# WS2812_MATRIX_1.net
KiCad netlist of a schematic drawn in Altium Designer
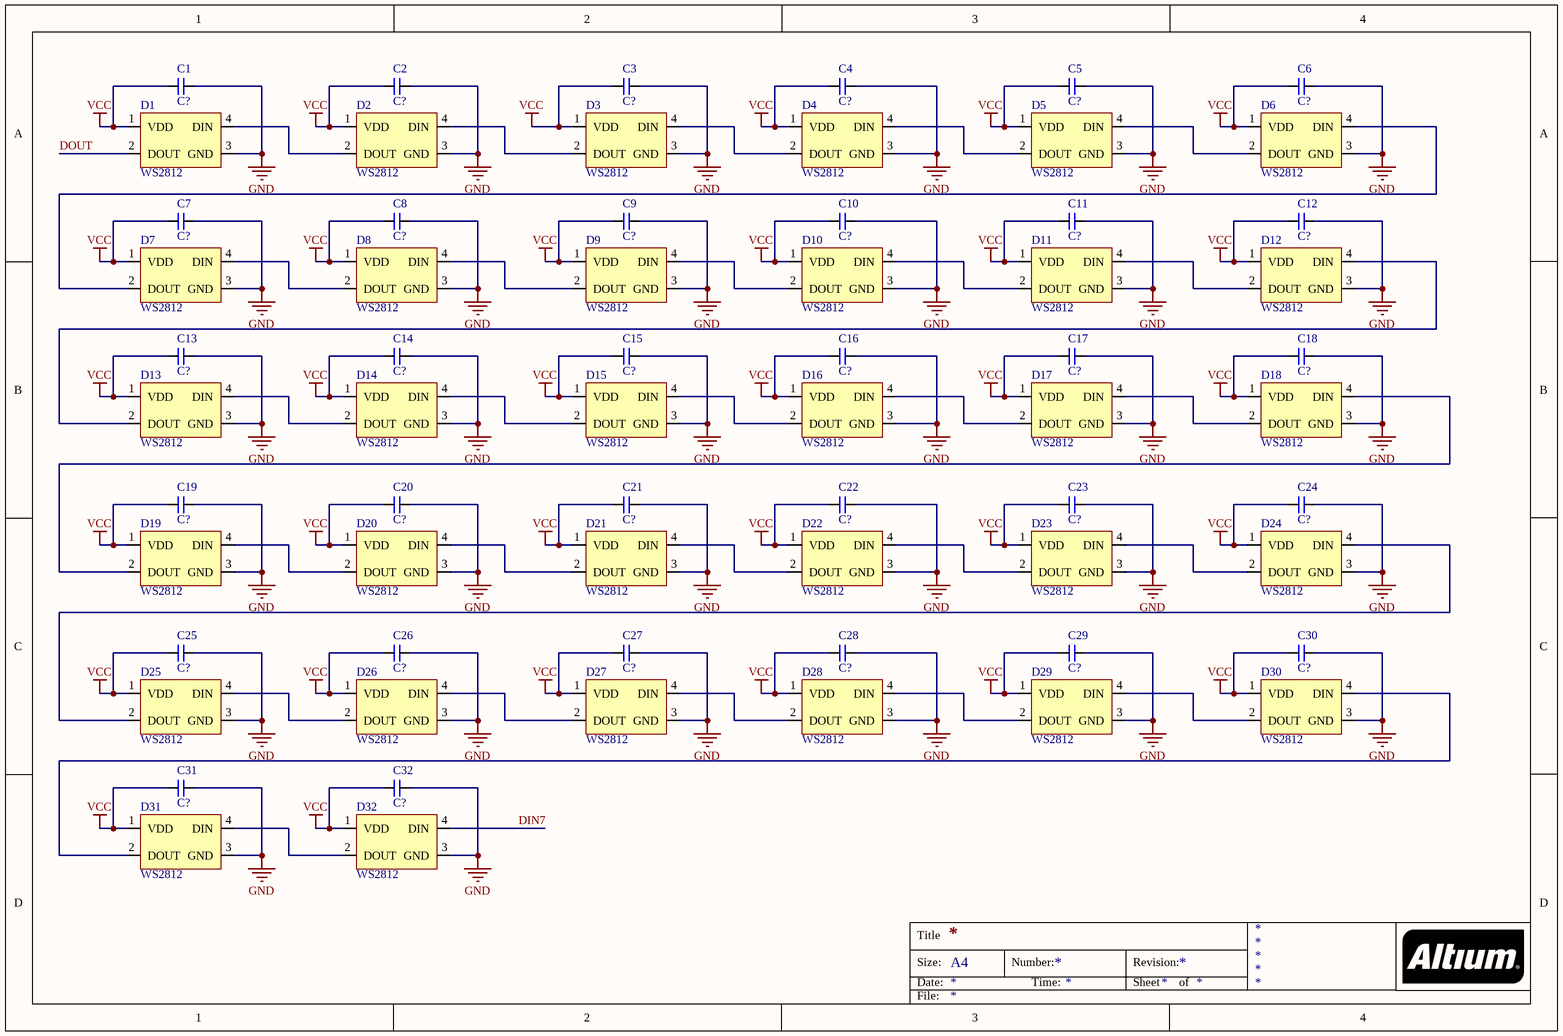
[diagram p0: WS2812_MATRIX_1.SchDoc]

(export (version "E")
  (design (tool "Eeschema 10.0.6"))
  (components
    (comp (ref "C1")
      (value "C?")
      (footprint "C0603")
      (description "Cap")
      (libsource (lib "SCH_Bacsic") (part "CAP"))
    )
    (comp (ref "C2")
      (value "C?")
      (footprint "C0603")
      (description "Cap")
      (libsource (lib "SCH_Bacsic") (part "CAP"))
    )
    (comp (ref "C3")
      (value "C?")
      (footprint "C0603")
      (description "Cap")
      (libsource (lib "SCH_Bacsic") (part "CAP"))
    )
    (comp (ref "C4")
      (value "C?")
      (footprint "C0603")
      (description "Cap")
      (libsource (lib "SCH_Bacsic") (part "CAP"))
    )
    (comp (ref "C5")
      (value "C?")
      (footprint "C0603")
      (description "Cap")
      (libsource (lib "SCH_Bacsic") (part "CAP"))
    )
    (comp (ref "C6")
      (value "C?")
      (footprint "C0603")
      (description "Cap")
      (libsource (lib "SCH_Bacsic") (part "CAP"))
    )
    (comp (ref "C7")
      (value "C?")
      (footprint "C0603")
      (description "Cap")
      (libsource (lib "SCH_Bacsic") (part "CAP"))
    )
    (comp (ref "C8")
      (value "C?")
      (footprint "C0603")
      (description "Cap")
      (libsource (lib "SCH_Bacsic") (part "CAP"))
    )
    (comp (ref "C9")
      (value "C?")
      (footprint "C0603")
      (description "Cap")
      (libsource (lib "SCH_Bacsic") (part "CAP"))
    )
    (comp (ref "C10")
      (value "C?")
      (footprint "C0603")
      (description "Cap")
      (libsource (lib "SCH_Bacsic") (part "CAP"))
    )
    (comp (ref "C11")
      (value "C?")
      (footprint "C0603")
      (description "Cap")
      (libsource (lib "SCH_Bacsic") (part "CAP"))
    )
    (comp (ref "C12")
      (value "C?")
      (footprint "C0603")
      (description "Cap")
      (libsource (lib "SCH_Bacsic") (part "CAP"))
    )
    (comp (ref "C13")
      (value "C?")
      (footprint "C0603")
      (description "Cap")
      (libsource (lib "SCH_Bacsic") (part "CAP"))
    )
    (comp (ref "C14")
      (value "C?")
      (footprint "C0603")
      (description "Cap")
      (libsource (lib "SCH_Bacsic") (part "CAP"))
    )
    (comp (ref "C15")
      (value "C?")
      (footprint "C0603")
      (description "Cap")
      (libsource (lib "SCH_Bacsic") (part "CAP"))
    )
    (comp (ref "C16")
      (value "C?")
      (footprint "C0603")
      (description "Cap")
      (libsource (lib "SCH_Bacsic") (part "CAP"))
    )
    (comp (ref "C17")
      (value "C?")
      (footprint "C0603")
      (description "Cap")
      (libsource (lib "SCH_Bacsic") (part "CAP"))
    )
    (comp (ref "C18")
      (value "C?")
      (footprint "C0603")
      (description "Cap")
      (libsource (lib "SCH_Bacsic") (part "CAP"))
    )
    (comp (ref "C19")
      (value "C?")
      (footprint "C0603")
      (description "Cap")
      (libsource (lib "SCH_Bacsic") (part "CAP"))
    )
    (comp (ref "C20")
      (value "C?")
      (footprint "C0603")
      (description "Cap")
      (libsource (lib "SCH_Bacsic") (part "CAP"))
    )
    (comp (ref "C21")
      (value "C?")
      (footprint "C0603")
      (description "Cap")
      (libsource (lib "SCH_Bacsic") (part "CAP"))
    )
    (comp (ref "C22")
      (value "C?")
      (footprint "C0603")
      (description "Cap")
      (libsource (lib "SCH_Bacsic") (part "CAP"))
    )
    (comp (ref "C23")
      (value "C?")
      (footprint "C0603")
      (description "Cap")
      (libsource (lib "SCH_Bacsic") (part "CAP"))
    )
    (comp (ref "C24")
      (value "C?")
      (footprint "C0603")
      (description "Cap")
      (libsource (lib "SCH_Bacsic") (part "CAP"))
    )
    (comp (ref "C25")
      (value "C?")
      (footprint "C0603")
      (description "Cap")
      (libsource (lib "SCH_Bacsic") (part "CAP"))
    )
    (comp (ref "C26")
      (value "C?")
      (footprint "C0603")
      (description "Cap")
      (libsource (lib "SCH_Bacsic") (part "CAP"))
    )
    (comp (ref "C27")
      (value "C?")
      (footprint "C0603")
      (description "Cap")
      (libsource (lib "SCH_Bacsic") (part "CAP"))
    )
    (comp (ref "C28")
      (value "C?")
      (footprint "C0603")
      (description "Cap")
      (libsource (lib "SCH_Bacsic") (part "CAP"))
    )
    (comp (ref "C29")
      (value "C?")
      (footprint "C0603")
      (description "Cap")
      (libsource (lib "SCH_Bacsic") (part "CAP"))
    )
    (comp (ref "C30")
      (value "C?")
      (footprint "C0603")
      (description "Cap")
      (libsource (lib "SCH_Bacsic") (part "CAP"))
    )
    (comp (ref "C31")
      (value "C?")
      (footprint "C0603")
      (description "Cap")
      (libsource (lib "SCH_Bacsic") (part "CAP"))
    )
    (comp (ref "C32")
      (value "C?")
      (footprint "C0603")
      (description "Cap")
      (libsource (lib "SCH_Bacsic") (part "CAP"))
    )
    (comp (ref "D1")
      (value "WS2812")
      (footprint "WS2812_3528")
      (libsource (lib "SCH_Bacsic") (part "WS2812"))
    )
    (comp (ref "D2")
      (value "WS2812")
      (footprint "WS2812_3528")
      (libsource (lib "SCH_Bacsic") (part "WS2812"))
    )
    (comp (ref "D3")
      (value "WS2812")
      (footprint "WS2812_3528")
      (libsource (lib "SCH_Bacsic") (part "WS2812"))
    )
    (comp (ref "D4")
      (value "WS2812")
      (footprint "WS2812_3528")
      (libsource (lib "SCH_Bacsic") (part "WS2812"))
    )
    (comp (ref "D5")
      (value "WS2812")
      (footprint "WS2812_3528")
      (libsource (lib "SCH_Bacsic") (part "WS2812"))
    )
    (comp (ref "D6")
      (value "WS2812")
      (footprint "WS2812_3528")
      (libsource (lib "SCH_Bacsic") (part "WS2812"))
    )
    (comp (ref "D7")
      (value "WS2812")
      (footprint "WS2812_3528")
      (libsource (lib "SCH_Bacsic") (part "WS2812"))
    )
    (comp (ref "D8")
      (value "WS2812")
      (footprint "WS2812_3528")
      (libsource (lib "SCH_Bacsic") (part "WS2812"))
    )
    (comp (ref "D9")
      (value "WS2812")
      (footprint "WS2812_3528")
      (libsource (lib "SCH_Bacsic") (part "WS2812"))
    )
    (comp (ref "D10")
      (value "WS2812")
      (footprint "WS2812_3528")
      (libsource (lib "SCH_Bacsic") (part "WS2812"))
    )
    (comp (ref "D11")
      (value "WS2812")
      (footprint "WS2812_3528")
      (libsource (lib "SCH_Bacsic") (part "WS2812"))
    )
    (comp (ref "D12")
      (value "WS2812")
      (footprint "WS2812_3528")
      (libsource (lib "SCH_Bacsic") (part "WS2812"))
    )
    (comp (ref "D13")
      (value "WS2812")
      (footprint "WS2812_3528")
      (libsource (lib "SCH_Bacsic") (part "WS2812"))
    )
    (comp (ref "D14")
      (value "WS2812")
      (footprint "WS2812_3528")
      (libsource (lib "SCH_Bacsic") (part "WS2812"))
    )
    (comp (ref "D15")
      (value "WS2812")
      (footprint "WS2812_3528")
      (libsource (lib "SCH_Bacsic") (part "WS2812"))
    )
    (comp (ref "D16")
      (value "WS2812")
      (footprint "WS2812_3528")
      (libsource (lib "SCH_Bacsic") (part "WS2812"))
    )
    (comp (ref "D17")
      (value "WS2812")
      (footprint "WS2812_3528")
      (libsource (lib "SCH_Bacsic") (part "WS2812"))
    )
    (comp (ref "D18")
      (value "WS2812")
      (footprint "WS2812_3528")
      (libsource (lib "SCH_Bacsic") (part "WS2812"))
    )
    (comp (ref "D19")
      (value "WS2812")
      (footprint "WS2812_3528")
      (libsource (lib "SCH_Bacsic") (part "WS2812"))
    )
    (comp (ref "D20")
      (value "WS2812")
      (footprint "WS2812_3528")
      (libsource (lib "SCH_Bacsic") (part "WS2812"))
    )
    (comp (ref "D21")
      (value "WS2812")
      (footprint "WS2812_3528")
      (libsource (lib "SCH_Bacsic") (part "WS2812"))
    )
    (comp (ref "D22")
      (value "WS2812")
      (footprint "WS2812_3528")
      (libsource (lib "SCH_Bacsic") (part "WS2812"))
    )
    (comp (ref "D23")
      (value "WS2812")
      (footprint "WS2812_3528")
      (libsource (lib "SCH_Bacsic") (part "WS2812"))
    )
    (comp (ref "D24")
      (value "WS2812")
      (footprint "WS2812_3528")
      (libsource (lib "SCH_Bacsic") (part "WS2812"))
    )
    (comp (ref "D25")
      (value "WS2812")
      (footprint "WS2812_3528")
      (libsource (lib "SCH_Bacsic") (part "WS2812"))
    )
    (comp (ref "D26")
      (value "WS2812")
      (footprint "WS2812_3528")
      (libsource (lib "SCH_Bacsic") (part "WS2812"))
    )
    (comp (ref "D27")
      (value "WS2812")
      (footprint "WS2812_3528")
      (libsource (lib "SCH_Bacsic") (part "WS2812"))
    )
    (comp (ref "D28")
      (value "WS2812")
      (footprint "WS2812_3528")
      (libsource (lib "SCH_Bacsic") (part "WS2812"))
    )
    (comp (ref "D29")
      (value "WS2812")
      (footprint "WS2812_3528")
      (libsource (lib "SCH_Bacsic") (part "WS2812"))
    )
    (comp (ref "D30")
      (value "WS2812")
      (footprint "WS2812_3528")
      (libsource (lib "SCH_Bacsic") (part "WS2812"))
    )
    (comp (ref "D31")
      (value "WS2812")
      (footprint "WS2812_3528")
      (libsource (lib "SCH_Bacsic") (part "WS2812"))
    )
    (comp (ref "D32")
      (value "WS2812")
      (footprint "WS2812_3528")
      (libsource (lib "SCH_Bacsic") (part "WS2812"))
    )
  )
  (nets
    (net (code "1") (name "/DIN7") (class "Default")
      (node (ref "D32") (pin "4") (pinfunction "DIN_4") (pintype "passive"))
    )
    (net (code "2") (name "/DOUT") (class "Default")
      (node (ref "D1") (pin "2") (pinfunction "DOUT_2") (pintype "passive"))
    )
    (net (code "3") (name "GND") (class "Default")
      (node (ref "C1") (pin "2") (pintype "passive"))
      (node (ref "C10") (pin "2") (pintype "passive"))
      (node (ref "C11") (pin "2") (pintype "passive"))
      (node (ref "C12") (pin "2") (pintype "passive"))
      (node (ref "C13") (pin "2") (pintype "passive"))
      (node (ref "C14") (pin "2") (pintype "passive"))
      (node (ref "C15") (pin "2") (pintype "passive"))
      (node (ref "C16") (pin "2") (pintype "passive"))
      (node (ref "C17") (pin "2") (pintype "passive"))
      (node (ref "C18") (pin "2") (pintype "passive"))
      (node (ref "C19") (pin "2") (pintype "passive"))
      (node (ref "C2") (pin "2") (pintype "passive"))
      (node (ref "C20") (pin "2") (pintype "passive"))
      (node (ref "C21") (pin "2") (pintype "passive"))
      (node (ref "C22") (pin "2") (pintype "passive"))
      (node (ref "C23") (pin "2") (pintype "passive"))
      (node (ref "C24") (pin "2") (pintype "passive"))
      (node (ref "C25") (pin "2") (pintype "passive"))
      (node (ref "C26") (pin "2") (pintype "passive"))
      (node (ref "C27") (pin "2") (pintype "passive"))
      (node (ref "C28") (pin "2") (pintype "passive"))
      (node (ref "C29") (pin "2") (pintype "passive"))
      (node (ref "C3") (pin "2") (pintype "passive"))
      (node (ref "C30") (pin "2") (pintype "passive"))
      (node (ref "C31") (pin "2") (pintype "passive"))
      (node (ref "C32") (pin "2") (pintype "passive"))
      (node (ref "C4") (pin "2") (pintype "passive"))
      (node (ref "C5") (pin "2") (pintype "passive"))
      (node (ref "C6") (pin "2") (pintype "passive"))
      (node (ref "C7") (pin "2") (pintype "passive"))
      (node (ref "C8") (pin "2") (pintype "passive"))
      (node (ref "C9") (pin "2") (pintype "passive"))
      (node (ref "D1") (pin "3") (pinfunction "GND_3") (pintype "passive"))
      (node (ref "D10") (pin "3") (pinfunction "GND_3") (pintype "passive"))
      (node (ref "D11") (pin "3") (pinfunction "GND_3") (pintype "passive"))
      (node (ref "D12") (pin "3") (pinfunction "GND_3") (pintype "passive"))
      (node (ref "D13") (pin "3") (pinfunction "GND_3") (pintype "passive"))
      (node (ref "D14") (pin "3") (pinfunction "GND_3") (pintype "passive"))
      (node (ref "D15") (pin "3") (pinfunction "GND_3") (pintype "passive"))
      (node (ref "D16") (pin "3") (pinfunction "GND_3") (pintype "passive"))
      (node (ref "D17") (pin "3") (pinfunction "GND_3") (pintype "passive"))
      (node (ref "D18") (pin "3") (pinfunction "GND_3") (pintype "passive"))
      (node (ref "D19") (pin "3") (pinfunction "GND_3") (pintype "passive"))
      (node (ref "D2") (pin "3") (pinfunction "GND_3") (pintype "passive"))
      (node (ref "D20") (pin "3") (pinfunction "GND_3") (pintype "passive"))
      (node (ref "D21") (pin "3") (pinfunction "GND_3") (pintype "passive"))
      (node (ref "D22") (pin "3") (pinfunction "GND_3") (pintype "passive"))
      (node (ref "D23") (pin "3") (pinfunction "GND_3") (pintype "passive"))
      (node (ref "D24") (pin "3") (pinfunction "GND_3") (pintype "passive"))
      (node (ref "D25") (pin "3") (pinfunction "GND_3") (pintype "passive"))
      (node (ref "D26") (pin "3") (pinfunction "GND_3") (pintype "passive"))
      (node (ref "D27") (pin "3") (pinfunction "GND_3") (pintype "passive"))
      (node (ref "D28") (pin "3") (pinfunction "GND_3") (pintype "passive"))
      (node (ref "D29") (pin "3") (pinfunction "GND_3") (pintype "passive"))
      (node (ref "D3") (pin "3") (pinfunction "GND_3") (pintype "passive"))
      (node (ref "D30") (pin "3") (pinfunction "GND_3") (pintype "passive"))
      (node (ref "D31") (pin "3") (pinfunction "GND_3") (pintype "passive"))
      (node (ref "D32") (pin "3") (pinfunction "GND_3") (pintype "passive"))
      (node (ref "D4") (pin "3") (pinfunction "GND_3") (pintype "passive"))
      (node (ref "D5") (pin "3") (pinfunction "GND_3") (pintype "passive"))
      (node (ref "D6") (pin "3") (pinfunction "GND_3") (pintype "passive"))
      (node (ref "D7") (pin "3") (pinfunction "GND_3") (pintype "passive"))
      (node (ref "D8") (pin "3") (pinfunction "GND_3") (pintype "passive"))
      (node (ref "D9") (pin "3") (pinfunction "GND_3") (pintype "passive"))
    )
    (net (code "4") (name "Net-(D1-DIN)") (class "Default")
      (node (ref "D1") (pin "4") (pinfunction "DIN_4") (pintype "passive"))
      (node (ref "D2") (pin "2") (pinfunction "DOUT_2") (pintype "passive"))
    )
    (net (code "5") (name "Net-(D2-DIN)") (class "Default")
      (node (ref "D2") (pin "4") (pinfunction "DIN_4") (pintype "passive"))
      (node (ref "D3") (pin "2") (pinfunction "DOUT_2") (pintype "passive"))
    )
    (net (code "6") (name "Net-(D3-DIN)") (class "Default")
      (node (ref "D3") (pin "4") (pinfunction "DIN_4") (pintype "passive"))
      (node (ref "D4") (pin "2") (pinfunction "DOUT_2") (pintype "passive"))
    )
    (net (code "7") (name "Net-(D4-DIN)") (class "Default")
      (node (ref "D4") (pin "4") (pinfunction "DIN_4") (pintype "passive"))
      (node (ref "D5") (pin "2") (pinfunction "DOUT_2") (pintype "passive"))
    )
    (net (code "8") (name "Net-(D5-DIN)") (class "Default")
      (node (ref "D5") (pin "4") (pinfunction "DIN_4") (pintype "passive"))
      (node (ref "D6") (pin "2") (pinfunction "DOUT_2") (pintype "passive"))
    )
    (net (code "9") (name "Net-(D6-DIN)") (class "Default")
      (node (ref "D6") (pin "4") (pinfunction "DIN_4") (pintype "passive"))
      (node (ref "D7") (pin "2") (pinfunction "DOUT_2") (pintype "passive"))
    )
    (net (code "10") (name "Net-(D7-DIN)") (class "Default")
      (node (ref "D7") (pin "4") (pinfunction "DIN_4") (pintype "passive"))
      (node (ref "D8") (pin "2") (pinfunction "DOUT_2") (pintype "passive"))
    )
    (net (code "11") (name "Net-(D8-DIN)") (class "Default")
      (node (ref "D8") (pin "4") (pinfunction "DIN_4") (pintype "passive"))
      (node (ref "D9") (pin "2") (pinfunction "DOUT_2") (pintype "passive"))
    )
    (net (code "12") (name "Net-(D10-DIN)") (class "Default")
      (node (ref "D10") (pin "4") (pinfunction "DIN_4") (pintype "passive"))
      (node (ref "D11") (pin "2") (pinfunction "DOUT_2") (pintype "passive"))
    )
    (net (code "13") (name "Net-(D10-DOUT)") (class "Default")
      (node (ref "D10") (pin "2") (pinfunction "DOUT_2") (pintype "passive"))
      (node (ref "D9") (pin "4") (pinfunction "DIN_4") (pintype "passive"))
    )
    (net (code "14") (name "Net-(D11-DIN)") (class "Default")
      (node (ref "D11") (pin "4") (pinfunction "DIN_4") (pintype "passive"))
      (node (ref "D12") (pin "2") (pinfunction "DOUT_2") (pintype "passive"))
    )
    (net (code "15") (name "Net-(D12-DIN)") (class "Default")
      (node (ref "D12") (pin "4") (pinfunction "DIN_4") (pintype "passive"))
      (node (ref "D13") (pin "2") (pinfunction "DOUT_2") (pintype "passive"))
    )
    (net (code "16") (name "Net-(D13-DIN)") (class "Default")
      (node (ref "D13") (pin "4") (pinfunction "DIN_4") (pintype "passive"))
      (node (ref "D14") (pin "2") (pinfunction "DOUT_2") (pintype "passive"))
    )
    (net (code "17") (name "Net-(D14-DIN)") (class "Default")
      (node (ref "D14") (pin "4") (pinfunction "DIN_4") (pintype "passive"))
      (node (ref "D15") (pin "2") (pinfunction "DOUT_2") (pintype "passive"))
    )
    (net (code "18") (name "Net-(D15-DIN)") (class "Default")
      (node (ref "D15") (pin "4") (pinfunction "DIN_4") (pintype "passive"))
      (node (ref "D16") (pin "2") (pinfunction "DOUT_2") (pintype "passive"))
    )
    (net (code "19") (name "Net-(D16-DIN)") (class "Default")
      (node (ref "D16") (pin "4") (pinfunction "DIN_4") (pintype "passive"))
      (node (ref "D17") (pin "2") (pinfunction "DOUT_2") (pintype "passive"))
    )
    (net (code "20") (name "Net-(D17-DIN)") (class "Default")
      (node (ref "D17") (pin "4") (pinfunction "DIN_4") (pintype "passive"))
      (node (ref "D18") (pin "2") (pinfunction "DOUT_2") (pintype "passive"))
    )
    (net (code "21") (name "Net-(D18-DIN)") (class "Default")
      (node (ref "D18") (pin "4") (pinfunction "DIN_4") (pintype "passive"))
      (node (ref "D19") (pin "2") (pinfunction "DOUT_2") (pintype "passive"))
    )
    (net (code "22") (name "Net-(D19-DIN)") (class "Default")
      (node (ref "D19") (pin "4") (pinfunction "DIN_4") (pintype "passive"))
      (node (ref "D20") (pin "2") (pinfunction "DOUT_2") (pintype "passive"))
    )
    (net (code "23") (name "Net-(D20-DIN)") (class "Default")
      (node (ref "D20") (pin "4") (pinfunction "DIN_4") (pintype "passive"))
      (node (ref "D21") (pin "2") (pinfunction "DOUT_2") (pintype "passive"))
    )
    (net (code "24") (name "Net-(D21-DIN)") (class "Default")
      (node (ref "D21") (pin "4") (pinfunction "DIN_4") (pintype "passive"))
      (node (ref "D22") (pin "2") (pinfunction "DOUT_2") (pintype "passive"))
    )
    (net (code "25") (name "Net-(D22-DIN)") (class "Default")
      (node (ref "D22") (pin "4") (pinfunction "DIN_4") (pintype "passive"))
      (node (ref "D23") (pin "2") (pinfunction "DOUT_2") (pintype "passive"))
    )
    (net (code "26") (name "Net-(D23-DIN)") (class "Default")
      (node (ref "D23") (pin "4") (pinfunction "DIN_4") (pintype "passive"))
      (node (ref "D24") (pin "2") (pinfunction "DOUT_2") (pintype "passive"))
    )
    (net (code "27") (name "Net-(D24-DIN)") (class "Default")
      (node (ref "D24") (pin "4") (pinfunction "DIN_4") (pintype "passive"))
      (node (ref "D25") (pin "2") (pinfunction "DOUT_2") (pintype "passive"))
    )
    (net (code "28") (name "Net-(D25-DIN)") (class "Default")
      (node (ref "D25") (pin "4") (pinfunction "DIN_4") (pintype "passive"))
      (node (ref "D26") (pin "2") (pinfunction "DOUT_2") (pintype "passive"))
    )
    (net (code "29") (name "Net-(D26-DIN)") (class "Default")
      (node (ref "D26") (pin "4") (pinfunction "DIN_4") (pintype "passive"))
      (node (ref "D27") (pin "2") (pinfunction "DOUT_2") (pintype "passive"))
    )
    (net (code "30") (name "Net-(D27-DIN)") (class "Default")
      (node (ref "D27") (pin "4") (pinfunction "DIN_4") (pintype "passive"))
      (node (ref "D28") (pin "2") (pinfunction "DOUT_2") (pintype "passive"))
    )
    (net (code "31") (name "Net-(D28-DIN)") (class "Default")
      (node (ref "D28") (pin "4") (pinfunction "DIN_4") (pintype "passive"))
      (node (ref "D29") (pin "2") (pinfunction "DOUT_2") (pintype "passive"))
    )
    (net (code "32") (name "Net-(D29-DIN)") (class "Default")
      (node (ref "D29") (pin "4") (pinfunction "DIN_4") (pintype "passive"))
      (node (ref "D30") (pin "2") (pinfunction "DOUT_2") (pintype "passive"))
    )
    (net (code "33") (name "Net-(D30-DIN)") (class "Default")
      (node (ref "D30") (pin "4") (pinfunction "DIN_4") (pintype "passive"))
      (node (ref "D31") (pin "2") (pinfunction "DOUT_2") (pintype "passive"))
    )
    (net (code "34") (name "Net-(D31-DIN)") (class "Default")
      (node (ref "D31") (pin "4") (pinfunction "DIN_4") (pintype "passive"))
      (node (ref "D32") (pin "2") (pinfunction "DOUT_2") (pintype "passive"))
    )
    (net (code "35") (name "VCC") (class "Default")
      (node (ref "C1") (pin "1") (pintype "passive"))
      (node (ref "C10") (pin "1") (pintype "passive"))
      (node (ref "C11") (pin "1") (pintype "passive"))
      (node (ref "C12") (pin "1") (pintype "passive"))
      (node (ref "C13") (pin "1") (pintype "passive"))
      (node (ref "C14") (pin "1") (pintype "passive"))
      (node (ref "C15") (pin "1") (pintype "passive"))
      (node (ref "C16") (pin "1") (pintype "passive"))
      (node (ref "C17") (pin "1") (pintype "passive"))
      (node (ref "C18") (pin "1") (pintype "passive"))
      (node (ref "C19") (pin "1") (pintype "passive"))
      (node (ref "C2") (pin "1") (pintype "passive"))
      (node (ref "C20") (pin "1") (pintype "passive"))
      (node (ref "C21") (pin "1") (pintype "passive"))
      (node (ref "C22") (pin "1") (pintype "passive"))
      (node (ref "C23") (pin "1") (pintype "passive"))
      (node (ref "C24") (pin "1") (pintype "passive"))
      (node (ref "C25") (pin "1") (pintype "passive"))
      (node (ref "C26") (pin "1") (pintype "passive"))
      (node (ref "C27") (pin "1") (pintype "passive"))
      (node (ref "C28") (pin "1") (pintype "passive"))
      (node (ref "C29") (pin "1") (pintype "passive"))
      (node (ref "C3") (pin "1") (pintype "passive"))
      (node (ref "C30") (pin "1") (pintype "passive"))
      (node (ref "C31") (pin "1") (pintype "passive"))
      (node (ref "C32") (pin "1") (pintype "passive"))
      (node (ref "C4") (pin "1") (pintype "passive"))
      (node (ref "C5") (pin "1") (pintype "passive"))
      (node (ref "C6") (pin "1") (pintype "passive"))
      (node (ref "C7") (pin "1") (pintype "passive"))
      (node (ref "C8") (pin "1") (pintype "passive"))
      (node (ref "C9") (pin "1") (pintype "passive"))
      (node (ref "D1") (pin "1") (pinfunction "VDD_1") (pintype "passive"))
      (node (ref "D10") (pin "1") (pinfunction "VDD_1") (pintype "passive"))
      (node (ref "D11") (pin "1") (pinfunction "VDD_1") (pintype "passive"))
      (node (ref "D12") (pin "1") (pinfunction "VDD_1") (pintype "passive"))
      (node (ref "D13") (pin "1") (pinfunction "VDD_1") (pintype "passive"))
      (node (ref "D14") (pin "1") (pinfunction "VDD_1") (pintype "passive"))
      (node (ref "D15") (pin "1") (pinfunction "VDD_1") (pintype "passive"))
      (node (ref "D16") (pin "1") (pinfunction "VDD_1") (pintype "passive"))
      (node (ref "D17") (pin "1") (pinfunction "VDD_1") (pintype "passive"))
      (node (ref "D18") (pin "1") (pinfunction "VDD_1") (pintype "passive"))
      (node (ref "D19") (pin "1") (pinfunction "VDD_1") (pintype "passive"))
      (node (ref "D2") (pin "1") (pinfunction "VDD_1") (pintype "passive"))
      (node (ref "D20") (pin "1") (pinfunction "VDD_1") (pintype "passive"))
      (node (ref "D21") (pin "1") (pinfunction "VDD_1") (pintype "passive"))
      (node (ref "D22") (pin "1") (pinfunction "VDD_1") (pintype "passive"))
      (node (ref "D23") (pin "1") (pinfunction "VDD_1") (pintype "passive"))
      (node (ref "D24") (pin "1") (pinfunction "VDD_1") (pintype "passive"))
      (node (ref "D25") (pin "1") (pinfunction "VDD_1") (pintype "passive"))
      (node (ref "D26") (pin "1") (pinfunction "VDD_1") (pintype "passive"))
      (node (ref "D27") (pin "1") (pinfunction "VDD_1") (pintype "passive"))
      (node (ref "D28") (pin "1") (pinfunction "VDD_1") (pintype "passive"))
      (node (ref "D29") (pin "1") (pinfunction "VDD_1") (pintype "passive"))
      (node (ref "D3") (pin "1") (pinfunction "VDD_1") (pintype "passive"))
      (node (ref "D30") (pin "1") (pinfunction "VDD_1") (pintype "passive"))
      (node (ref "D31") (pin "1") (pinfunction "VDD_1") (pintype "passive"))
      (node (ref "D32") (pin "1") (pinfunction "VDD_1") (pintype "passive"))
      (node (ref "D4") (pin "1") (pinfunction "VDD_1") (pintype "passive"))
      (node (ref "D5") (pin "1") (pinfunction "VDD_1") (pintype "passive"))
      (node (ref "D6") (pin "1") (pinfunction "VDD_1") (pintype "passive"))
      (node (ref "D7") (pin "1") (pinfunction "VDD_1") (pintype "passive"))
      (node (ref "D8") (pin "1") (pinfunction "VDD_1") (pintype "passive"))
      (node (ref "D9") (pin "1") (pinfunction "VDD_1") (pintype "passive"))
    )
  )
)
